# Midi_full.net
KiCad netlist of a schematic drawn in Altium Designer
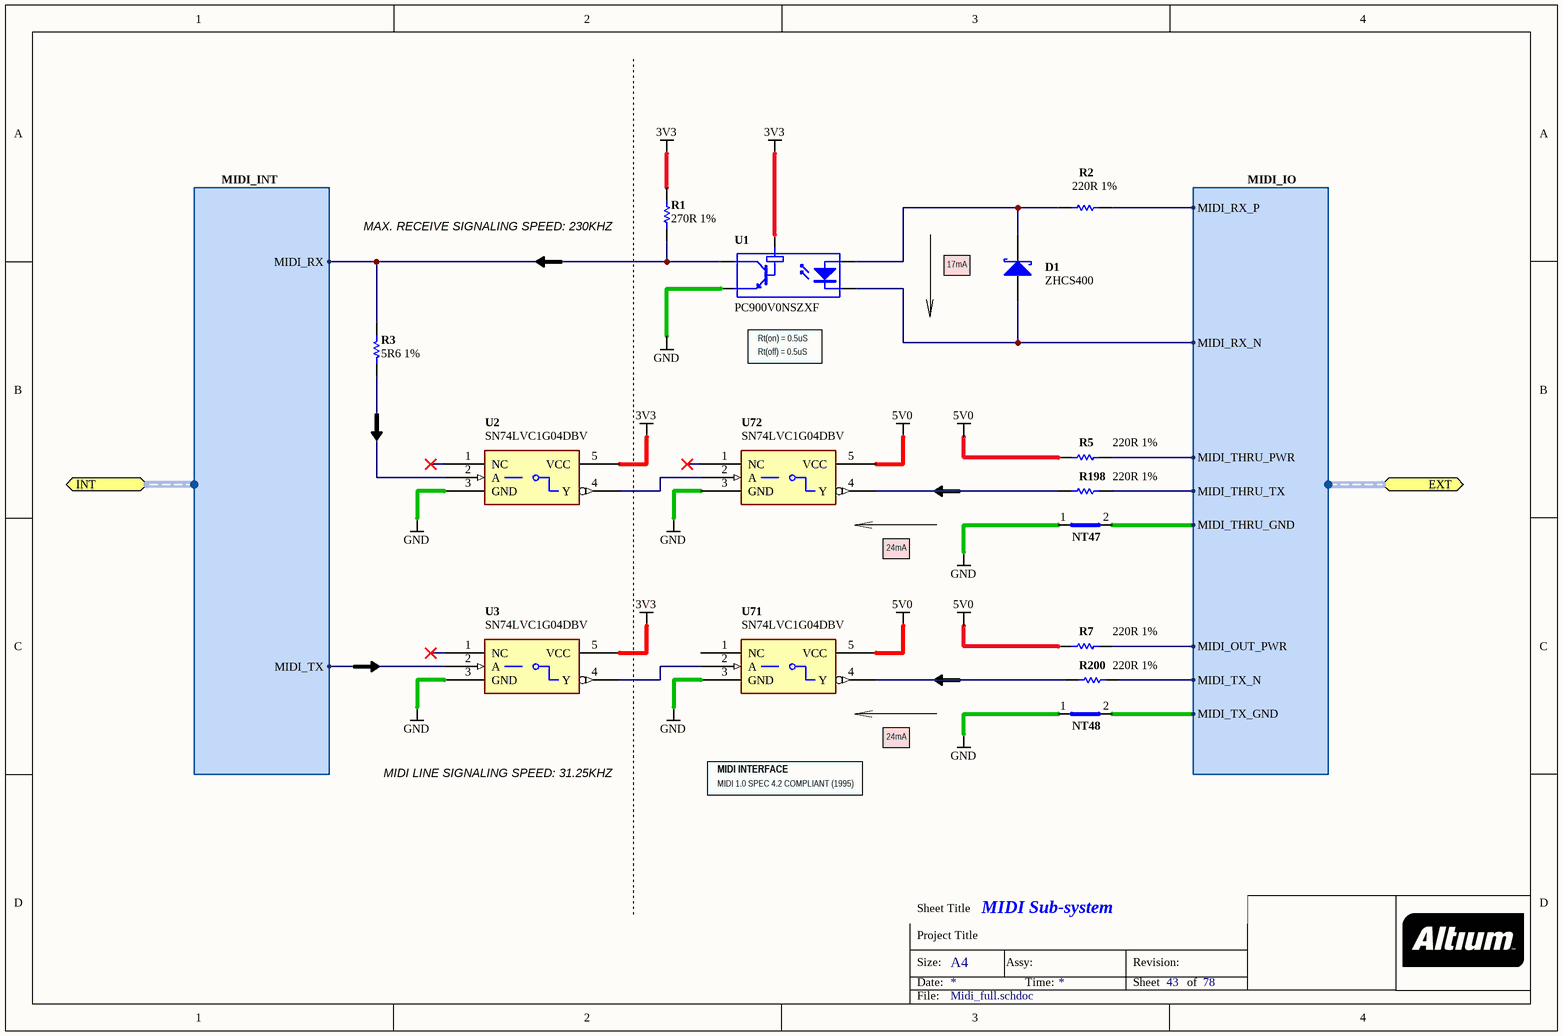
[diagram p0: Midi_full.schdoc]

(export (version "E")
  (design (tool "Eeschema 10.0.6"))
  (components
    (comp (ref "D1")
      (value "ZHCS400")
      (footprint "SOD323")
      (description "Schottky Diode, 400mA")
      (libsource (lib "AltiumDesignLibrary") (part "DIO-SCHOTTKY-1S"))
    )
    (comp (ref "NT47")
      (value "Net Tie SMT2")
      (footprint "NETTIE-SMT2-8X8")
      (description "Net-Tie, Surface Mount, 2 x 0.4mm x 0.2mm SMT Pads - For 0.2mm Track")
      (libsource (lib "AltiumDesignLibrary") (part "NETTIE-SMT2"))
    )
    (comp (ref "NT48")
      (value "Net Tie SMT2")
      (footprint "NETTIE-SMT2-8X8")
      (description "Net-Tie, Surface Mount, 2 x 0.4mm x 0.2mm SMT Pads - For 0.2mm Track")
      (libsource (lib "AltiumDesignLibrary") (part "NETTIE-SMT2"))
    )
    (comp (ref "R1")
      (value "270R 1%")
      (footprint "RESC1005-STAR")
      (description "Resistor, 270R 1% 0402 (1005)")
      (fields (field (name "TOLERANCE") "1 %"))
      (libsource (lib "AltiumDesignLibrary") (part "RES"))
    )
    (comp (ref "R2")
      (value "220R 1%")
      (footprint "RESC1005-STAR")
      (description "Resistor, 220R 1% 0402 (1005)")
      (fields (field (name "TOLERANCE") "1 %"))
      (libsource (lib "AltiumDesignLibrary") (part "RES"))
    )
    (comp (ref "R3")
      (value "5R6 1%")
      (footprint "RESC1005-STAR")
      (description "Resistor, 5R6 1% 0402 (1005)")
      (fields (field (name "TOLERANCE") "1 %"))
      (libsource (lib "AltiumDesignLibrary") (part "RES"))
    )
    (comp (ref "R5")
      (value "220R 1%")
      (footprint "RESC1005-STAR")
      (description "Resistor, 220R 1% 0402 (1005)")
      (fields (field (name "TOLERANCE") "1 %"))
      (libsource (lib "AltiumDesignLibrary") (part "RES"))
    )
    (comp (ref "R7")
      (value "220R 1%")
      (footprint "RESC1005-STAR")
      (description "Resistor, 220R 1% 0402 (1005)")
      (fields (field (name "TOLERANCE") "1 %"))
      (libsource (lib "AltiumDesignLibrary") (part "RES"))
    )
    (comp (ref "R198")
      (value "220R 1%")
      (footprint "RESC1005-STAR")
      (description "Resistor, 220R 1% 0402 (1005)")
      (fields (field (name "TOLERANCE") "1 %"))
      (libsource (lib "AltiumDesignLibrary") (part "RES"))
    )
    (comp (ref "R200")
      (value "220R 1%")
      (footprint "RESC1005-STAR")
      (description "Resistor, 220R 1% 0402 (1005)")
      (fields (field (name "TOLERANCE") "1 %"))
      (libsource (lib "AltiumDesignLibrary") (part "RES"))
    )
    (comp (ref "U1")
      (value "PC900V0NSZXF")
      (footprint "H11L1SR2VM")
      (description "OPTOISOLATOR; SMD; Digital Output, Normal OFF  Operation")
      (libsource (lib "AltiumDesignLibrary") (part "PC900V"))
    )
    (comp (ref "U2")
      (value "SN74LVC1G04DBV")
      (footprint "SOT95P280-5")
      (description "SN74LVC1G04DBV, Single Inverter Gate, 1.65-V to 5.5-V")
      (libsource (lib "AltiumDesignLibrary") (part "SN74LVC1G04DBV"))
    )
    (comp (ref "U3")
      (value "SN74LVC1G04DBV")
      (footprint "SOT95P280-5")
      (description "SN74LVC1G04DBV, Single Inverter Gate, 1.65-V to 5.5-V")
      (libsource (lib "AltiumDesignLibrary") (part "SN74LVC1G04DBV"))
    )
    (comp (ref "U71")
      (value "SN74LVC1G04DBV")
      (footprint "SOT95P280-5")
      (description "SN74LVC1G04DBV, Single Inverter Gate, 1.65-V to 5.5-V")
      (libsource (lib "AltiumDesignLibrary") (part "SN74LVC1G04DBV"))
    )
    (comp (ref "U72")
      (value "SN74LVC1G04DBV")
      (footprint "SOT95P280-5")
      (description "SN74LVC1G04DBV, Single Inverter Gate, 1.65-V to 5.5-V")
      (libsource (lib "AltiumDesignLibrary") (part "SN74LVC1G04DBV"))
    )
  )
  (nets
    (net (code "3") (name "/MIDI_OUT_PWR") (class "Default")
      (node (ref "R7") (pin "2") (pinfunction "2_2") (pintype "passive"))
    )
    (net (code "4") (name "/MIDI_RX") (class "Default")
      (node (ref "R1") (pin "1") (pinfunction "1_1") (pintype "passive"))
      (node (ref "R3") (pin "2") (pinfunction "2_2") (pintype "passive"))
      (node (ref "U1") (pin "4") (pinfunction "Vo_4") (pintype "passive"))
    )
    (net (code "5") (name "/MIDI_RX_N") (class "Default")
      (node (ref "D1") (pin "1") (pinfunction "A_1") (pintype "passive"))
      (node (ref "U1") (pin "2") (pinfunction "K_2") (pintype "passive"))
    )
    (net (code "6") (name "/MIDI_RX_P") (class "Default")
      (node (ref "R2") (pin "2") (pinfunction "2_2") (pintype "passive"))
    )
    (net (code "7") (name "/MIDI_THRU_GND") (class "Default")
      (node (ref "NT47") (pin "2") (pinfunction "Net2_2") (pintype "passive"))
    )
    (net (code "8") (name "/MIDI_THRU_PWR") (class "Default")
      (node (ref "R5") (pin "2") (pinfunction "2_2") (pintype "passive"))
    )
    (net (code "9") (name "/MIDI_THRU_TX") (class "Default")
      (node (ref "R198") (pin "2") (pinfunction "2_2") (pintype "passive"))
    )
    (net (code "10") (name "/MIDI_TX") (class "Default")
      (node (ref "U3") (pin "2") (pinfunction "A_2") (pintype "input"))
    )
    (net (code "11") (name "/MIDI_TX_GND") (class "Default")
      (node (ref "NT48") (pin "2") (pinfunction "Net2_2") (pintype "passive"))
    )
    (net (code "12") (name "/MIDI_TX_N") (class "Default")
      (node (ref "R200") (pin "2") (pinfunction "2_2") (pintype "passive"))
    )
    (net (code "15") (name "3V3") (class "Default")
      (node (ref "R1") (pin "2") (pinfunction "2_2") (pintype "passive"))
      (node (ref "U1") (pin "6") (pinfunction "Vcc_6") (pintype "passive"))
      (node (ref "U2") (pin "5") (pinfunction "VCC_5") (pintype "power_in"))
      (node (ref "U3") (pin "5") (pinfunction "VCC_5") (pintype "power_in"))
    )
    (net (code "16") (name "5V0") (class "Default")
      (node (ref "R5") (pin "1") (pinfunction "1_1") (pintype "passive"))
      (node (ref "R7") (pin "1") (pinfunction "1_1") (pintype "passive"))
      (node (ref "U71") (pin "5") (pinfunction "VCC_5") (pintype "power_in"))
      (node (ref "U72") (pin "5") (pinfunction "VCC_5") (pintype "power_in"))
    )
    (net (code "17") (name "GND") (class "Default")
      (node (ref "NT47") (pin "1") (pinfunction "Net1_1") (pintype "passive"))
      (node (ref "NT48") (pin "1") (pinfunction "Net1_1") (pintype "passive"))
      (node (ref "U1") (pin "5") (pinfunction "GND_5") (pintype "passive"))
      (node (ref "U2") (pin "3") (pinfunction "GND_3") (pintype "power_in"))
      (node (ref "U3") (pin "3") (pinfunction "GND_3") (pintype "power_in"))
      (node (ref "U71") (pin "3") (pinfunction "GND_3") (pintype "power_in"))
      (node (ref "U72") (pin "3") (pinfunction "GND_3") (pintype "power_in"))
    )
    (net (code "18") (name "Net-(D1-K)") (class "Default")
      (node (ref "D1") (pin "2") (pinfunction "K_2") (pintype "passive"))
      (node (ref "R2") (pin "1") (pinfunction "1_1") (pintype "passive"))
      (node (ref "U1") (pin "1") (pinfunction "A_1") (pintype "passive"))
    )
    (net (code "19") (name "Net-(U2-A)") (class "Default")
      (node (ref "R3") (pin "1") (pinfunction "1_1") (pintype "passive"))
      (node (ref "U2") (pin "2") (pinfunction "A_2") (pintype "input"))
    )
    (net (code "20") (name "Net-(U2-Y)") (class "Default")
      (node (ref "U2") (pin "4") (pinfunction "Y_4") (pintype "output"))
      (node (ref "U72") (pin "2") (pinfunction "A_2") (pintype "input"))
    )
    (net (code "21") (name "Net-(U3-Y)") (class "Default")
      (node (ref "U3") (pin "4") (pinfunction "Y_4") (pintype "output"))
      (node (ref "U71") (pin "2") (pinfunction "A_2") (pintype "input"))
    )
    (net (code "22") (name "Net-(U71-Y)") (class "Default")
      (node (ref "R200") (pin "1") (pinfunction "1_1") (pintype "passive"))
      (node (ref "U71") (pin "4") (pinfunction "Y_4") (pintype "output"))
    )
    (net (code "23") (name "Net-(U72-Y)") (class "Default")
      (node (ref "R198") (pin "1") (pinfunction "1_1") (pintype "passive"))
      (node (ref "U72") (pin "4") (pinfunction "Y_4") (pintype "output"))
    )
    (net (code "24") (name "unconnected-(U2-NC-Pad1)") (class "Default")
      (node (ref "U2") (pin "1") (pinfunction "NC_1") (pintype "passive+no_connect"))
    )
    (net (code "25") (name "unconnected-(U3-NC-Pad1)") (class "Default")
      (node (ref "U3") (pin "1") (pinfunction "NC_1") (pintype "passive+no_connect"))
    )
    (net (code "26") (name "unconnected-(U71-NC-Pad1)") (class "Default")
      (node (ref "U71") (pin "1") (pinfunction "NC_1") (pintype "passive"))
    )
    (net (code "27") (name "unconnected-(U72-NC-Pad1)") (class "Default")
      (node (ref "U72") (pin "1") (pinfunction "NC_1") (pintype "passive+no_connect"))
    )
  )
)
